# W500A.net
KiCad netlist of a schematic drawn in EAGLE
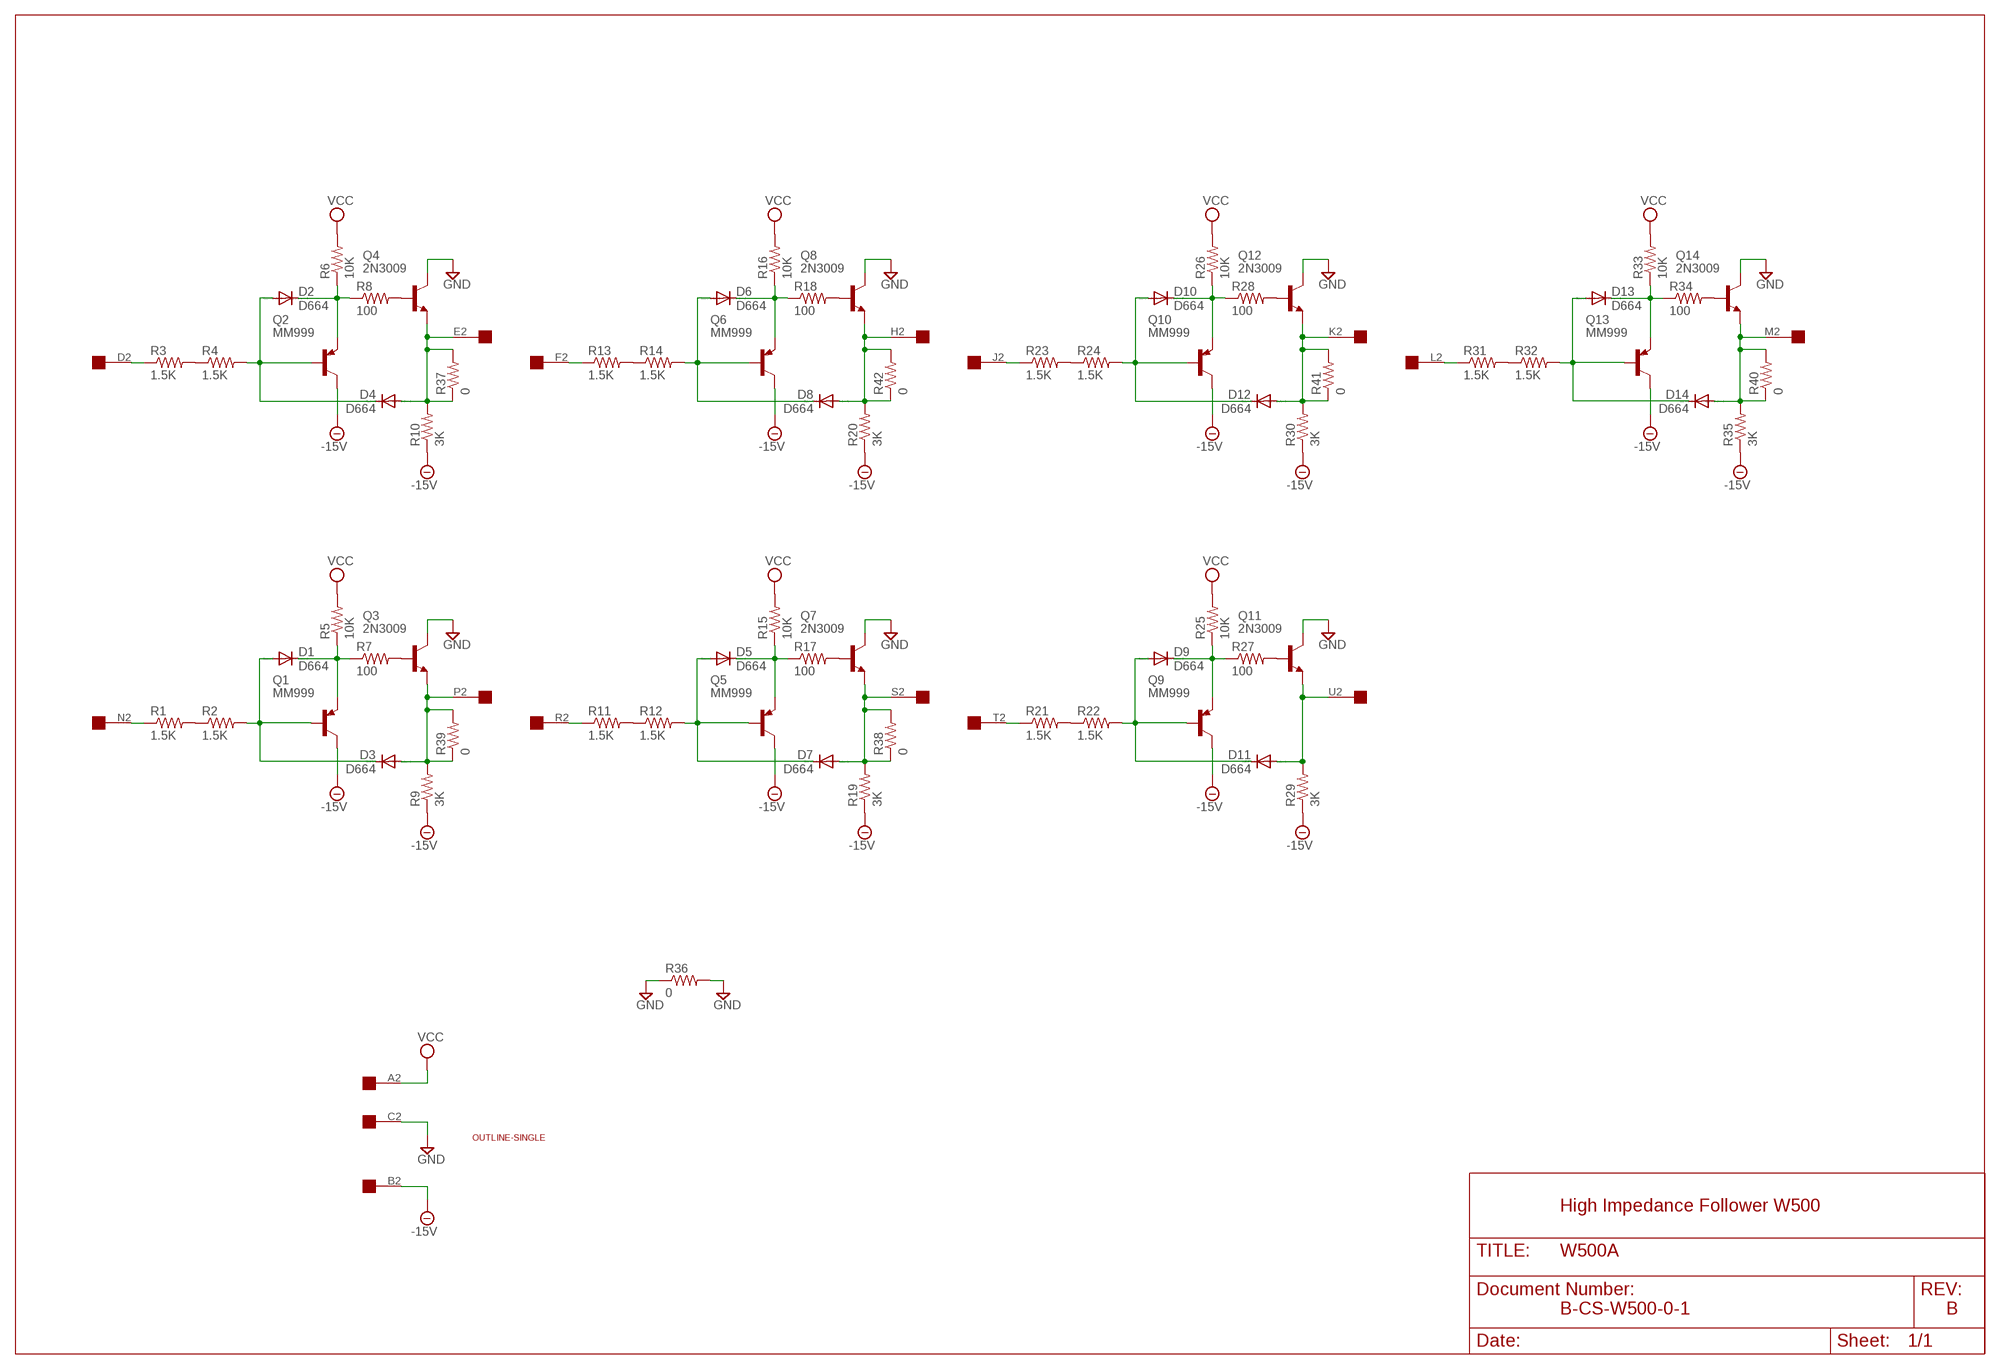
[diagram p0: schematic, sheet 1]

(export (version "E")
  (design (tool "Eeschema 10.0.6"))
  (components
    (comp (ref "D1")
      (value "D664")
      (footprint "eagle-import:DO35-10")
      (libsource (lib "eagle-import") (part "DIODE-DO35-10"))
    )
    (comp (ref "D2")
      (value "D664")
      (footprint "eagle-import:DO35-10")
      (libsource (lib "eagle-import") (part "DIODE-DO35-10"))
    )
    (comp (ref "D3")
      (value "D664")
      (footprint "eagle-import:DO35-10")
      (libsource (lib "eagle-import") (part "DIODE-DO35-10"))
    )
    (comp (ref "D4")
      (value "D664")
      (footprint "eagle-import:DO35-10")
      (libsource (lib "eagle-import") (part "DIODE-DO35-10"))
    )
    (comp (ref "D5")
      (value "D664")
      (footprint "eagle-import:DO35-10")
      (libsource (lib "eagle-import") (part "DIODE-DO35-10"))
    )
    (comp (ref "D6")
      (value "D664")
      (footprint "eagle-import:DO35-10")
      (libsource (lib "eagle-import") (part "DIODE-DO35-10"))
    )
    (comp (ref "D7")
      (value "D664")
      (footprint "eagle-import:DO35-10")
      (libsource (lib "eagle-import") (part "DIODE-DO35-10"))
    )
    (comp (ref "D8")
      (value "D664")
      (footprint "eagle-import:DO35-10")
      (libsource (lib "eagle-import") (part "DIODE-DO35-10"))
    )
    (comp (ref "D9")
      (value "D664")
      (footprint "eagle-import:DO35-10")
      (libsource (lib "eagle-import") (part "DIODE-DO35-10"))
    )
    (comp (ref "D10")
      (value "D664")
      (footprint "eagle-import:DO35-10")
      (libsource (lib "eagle-import") (part "DIODE-DO35-10"))
    )
    (comp (ref "D11")
      (value "D664")
      (footprint "eagle-import:DO35-10")
      (libsource (lib "eagle-import") (part "DIODE-DO35-10"))
    )
    (comp (ref "D12")
      (value "D664")
      (footprint "eagle-import:DO35-10")
      (libsource (lib "eagle-import") (part "DIODE-DO35-10"))
    )
    (comp (ref "D13")
      (value "D664")
      (footprint "eagle-import:DO35-10")
      (libsource (lib "eagle-import") (part "DIODE-DO35-10"))
    )
    (comp (ref "D14")
      (value "D664")
      (footprint "eagle-import:DO35-10")
      (libsource (lib "eagle-import") (part "DIODE-DO35-10"))
    )
    (comp (ref "Q1")
      (value "MM999")
      (footprint "eagle-import:TO5")
      (libsource (lib "eagle-import") (part "-PNP-TO5"))
    )
    (comp (ref "Q2")
      (value "MM999")
      (footprint "eagle-import:TO5")
      (libsource (lib "eagle-import") (part "-PNP-TO5"))
    )
    (comp (ref "Q3")
      (value "2N3009")
      (footprint "eagle-import:TO5")
      (libsource (lib "eagle-import") (part "-NPN-TO5"))
    )
    (comp (ref "Q4")
      (value "2N3009")
      (footprint "eagle-import:TO5")
      (libsource (lib "eagle-import") (part "-NPN-TO5"))
    )
    (comp (ref "Q5")
      (value "MM999")
      (footprint "eagle-import:TO5")
      (libsource (lib "eagle-import") (part "-PNP-TO5"))
    )
    (comp (ref "Q6")
      (value "MM999")
      (footprint "eagle-import:TO5")
      (libsource (lib "eagle-import") (part "-PNP-TO5"))
    )
    (comp (ref "Q7")
      (value "2N3009")
      (footprint "eagle-import:TO5")
      (libsource (lib "eagle-import") (part "-NPN-TO5"))
    )
    (comp (ref "Q8")
      (value "2N3009")
      (footprint "eagle-import:TO5")
      (libsource (lib "eagle-import") (part "-NPN-TO5"))
    )
    (comp (ref "Q9")
      (value "MM999")
      (footprint "eagle-import:TO5")
      (libsource (lib "eagle-import") (part "-PNP-TO5"))
    )
    (comp (ref "Q10")
      (value "MM999")
      (footprint "eagle-import:TO5")
      (libsource (lib "eagle-import") (part "-PNP-TO5"))
    )
    (comp (ref "Q11")
      (value "2N3009")
      (footprint "eagle-import:TO5")
      (libsource (lib "eagle-import") (part "-NPN-TO5"))
    )
    (comp (ref "Q12")
      (value "2N3009")
      (footprint "eagle-import:TO5")
      (libsource (lib "eagle-import") (part "-NPN-TO5"))
    )
    (comp (ref "Q13")
      (value "MM999")
      (footprint "eagle-import:TO5")
      (libsource (lib "eagle-import") (part "-PNP-TO5"))
    )
    (comp (ref "Q14")
      (value "2N3009")
      (footprint "eagle-import:TO5")
      (libsource (lib "eagle-import") (part "-NPN-TO5"))
    )
    (comp (ref "R1")
      (value "1.5K")
      (footprint "eagle-import:0207_10")
      (libsource (lib "eagle-import") (part "R-US_0207/10"))
    )
    (comp (ref "R2")
      (value "1.5K")
      (footprint "eagle-import:0207_10")
      (libsource (lib "eagle-import") (part "R-US_0207/10"))
    )
    (comp (ref "R3")
      (value "1.5K")
      (footprint "eagle-import:0207_10")
      (libsource (lib "eagle-import") (part "R-US_0207/10"))
    )
    (comp (ref "R4")
      (value "1.5K")
      (footprint "eagle-import:0207_10")
      (libsource (lib "eagle-import") (part "R-US_0207/10"))
    )
    (comp (ref "R5")
      (value "10K")
      (footprint "eagle-import:0207_10")
      (libsource (lib "eagle-import") (part "R-US_0207/10"))
    )
    (comp (ref "R6")
      (value "10K")
      (footprint "eagle-import:0207_10")
      (libsource (lib "eagle-import") (part "R-US_0207/10"))
    )
    (comp (ref "R7")
      (value "100")
      (footprint "eagle-import:0207_10")
      (libsource (lib "eagle-import") (part "R-US_0207/10"))
    )
    (comp (ref "R8")
      (value "100")
      (footprint "eagle-import:0207_10")
      (libsource (lib "eagle-import") (part "R-US_0207/10"))
    )
    (comp (ref "R9")
      (value "3K")
      (footprint "eagle-import:0207_10")
      (libsource (lib "eagle-import") (part "R-US_0207/10"))
    )
    (comp (ref "R10")
      (value "3K")
      (footprint "eagle-import:0207_10")
      (libsource (lib "eagle-import") (part "R-US_0207/10"))
    )
    (comp (ref "R11")
      (value "1.5K")
      (footprint "eagle-import:0207_10")
      (libsource (lib "eagle-import") (part "R-US_0207/10"))
    )
    (comp (ref "R12")
      (value "1.5K")
      (footprint "eagle-import:0207_10")
      (libsource (lib "eagle-import") (part "R-US_0207/10"))
    )
    (comp (ref "R13")
      (value "1.5K")
      (footprint "eagle-import:0207_10")
      (libsource (lib "eagle-import") (part "R-US_0207/10"))
    )
    (comp (ref "R14")
      (value "1.5K")
      (footprint "eagle-import:0207_10")
      (libsource (lib "eagle-import") (part "R-US_0207/10"))
    )
    (comp (ref "R15")
      (value "10K")
      (footprint "eagle-import:0207_10")
      (libsource (lib "eagle-import") (part "R-US_0207/10"))
    )
    (comp (ref "R16")
      (value "10K")
      (footprint "eagle-import:0207_10")
      (libsource (lib "eagle-import") (part "R-US_0207/10"))
    )
    (comp (ref "R17")
      (value "100")
      (footprint "eagle-import:0207_10")
      (libsource (lib "eagle-import") (part "R-US_0207/10"))
    )
    (comp (ref "R18")
      (value "100")
      (footprint "eagle-import:0207_10")
      (libsource (lib "eagle-import") (part "R-US_0207/10"))
    )
    (comp (ref "R19")
      (value "3K")
      (footprint "eagle-import:0207_10")
      (libsource (lib "eagle-import") (part "R-US_0207/10"))
    )
    (comp (ref "R20")
      (value "3K")
      (footprint "eagle-import:0207_10")
      (libsource (lib "eagle-import") (part "R-US_0207/10"))
    )
    (comp (ref "R21")
      (value "1.5K")
      (footprint "eagle-import:0207_10")
      (libsource (lib "eagle-import") (part "R-US_0207/10"))
    )
    (comp (ref "R22")
      (value "1.5K")
      (footprint "eagle-import:0207_10")
      (libsource (lib "eagle-import") (part "R-US_0207/10"))
    )
    (comp (ref "R23")
      (value "1.5K")
      (footprint "eagle-import:0207_10")
      (libsource (lib "eagle-import") (part "R-US_0207/10"))
    )
    (comp (ref "R24")
      (value "1.5K")
      (footprint "eagle-import:0207_10")
      (libsource (lib "eagle-import") (part "R-US_0207/10"))
    )
    (comp (ref "R25")
      (value "10K")
      (footprint "eagle-import:0207_10")
      (libsource (lib "eagle-import") (part "R-US_0207/10"))
    )
    (comp (ref "R26")
      (value "10K")
      (footprint "eagle-import:0207_10")
      (libsource (lib "eagle-import") (part "R-US_0207/10"))
    )
    (comp (ref "R27")
      (value "100")
      (footprint "eagle-import:0207_10")
      (libsource (lib "eagle-import") (part "R-US_0207/10"))
    )
    (comp (ref "R28")
      (value "100")
      (footprint "eagle-import:0207_10")
      (libsource (lib "eagle-import") (part "R-US_0207/10"))
    )
    (comp (ref "R29")
      (value "3K")
      (footprint "eagle-import:0207_10")
      (libsource (lib "eagle-import") (part "R-US_0207/10"))
    )
    (comp (ref "R30")
      (value "3K")
      (footprint "eagle-import:0207_10")
      (libsource (lib "eagle-import") (part "R-US_0207/10"))
    )
    (comp (ref "R31")
      (value "1.5K")
      (footprint "eagle-import:0207_10")
      (libsource (lib "eagle-import") (part "R-US_0207/10"))
    )
    (comp (ref "R32")
      (value "1.5K")
      (footprint "eagle-import:0207_10")
      (libsource (lib "eagle-import") (part "R-US_0207/10"))
    )
    (comp (ref "R33")
      (value "10K")
      (footprint "eagle-import:0207_10")
      (libsource (lib "eagle-import") (part "R-US_0207/10"))
    )
    (comp (ref "R34")
      (value "100")
      (footprint "eagle-import:0207_10")
      (libsource (lib "eagle-import") (part "R-US_0207/10"))
    )
    (comp (ref "R35")
      (value "3K")
      (footprint "eagle-import:0207_10")
      (libsource (lib "eagle-import") (part "R-US_0207/10"))
    )
    (comp (ref "R36")
      (value "0")
      (footprint "eagle-import:0207_10")
      (libsource (lib "eagle-import") (part "R-US_0207/10"))
    )
    (comp (ref "R37")
      (value "0")
      (footprint "eagle-import:0207_10")
      (libsource (lib "eagle-import") (part "R-US_0207/10"))
    )
    (comp (ref "R38")
      (value "0")
      (footprint "eagle-import:0207_10")
      (libsource (lib "eagle-import") (part "R-US_0207/10"))
    )
    (comp (ref "R39")
      (value "0")
      (footprint "eagle-import:0207_10")
      (libsource (lib "eagle-import") (part "R-US_0207/10"))
    )
    (comp (ref "R40")
      (value "0")
      (footprint "eagle-import:0207_10")
      (libsource (lib "eagle-import") (part "R-US_0207/10"))
    )
    (comp (ref "R41")
      (value "0")
      (footprint "eagle-import:0207_10")
      (libsource (lib "eagle-import") (part "R-US_0207/10"))
    )
    (comp (ref "R42")
      (value "0")
      (footprint "eagle-import:0207_10")
      (libsource (lib "eagle-import") (part "R-US_0207/10"))
    )
    (comp (ref "U$1")
      (value "OUTLINE-SINGLE")
      (footprint "eagle-import:SINGLE")
      (libsource (lib "eagle-import") (part "OUTLINE-SINGLE"))
    )
    (comp (ref "U$2")
      (value "EDGE-1")
      (footprint "eagle-import:EDGE-CON1")
      (libsource (lib "eagle-import") (part "EDGE-1"))
    )
  )
  (nets
    (net (code "1") (name "-15V") (class "Default")
      (node (ref "Q1") (pin "3") (pinfunction "C_3") (pintype "passive"))
      (node (ref "Q10") (pin "3") (pinfunction "C_3") (pintype "passive"))
      (node (ref "Q13") (pin "3") (pinfunction "C_3") (pintype "passive"))
      (node (ref "Q2") (pin "3") (pinfunction "C_3") (pintype "passive"))
      (node (ref "Q5") (pin "3") (pinfunction "C_3") (pintype "passive"))
      (node (ref "Q6") (pin "3") (pinfunction "C_3") (pintype "passive"))
      (node (ref "Q9") (pin "3") (pinfunction "C_3") (pintype "passive"))
      (node (ref "R10") (pin "1") (pinfunction "1_1") (pintype "passive"))
      (node (ref "R19") (pin "1") (pinfunction "1_1") (pintype "passive"))
      (node (ref "R20") (pin "1") (pinfunction "1_1") (pintype "passive"))
      (node (ref "R29") (pin "1") (pinfunction "1_1") (pintype "passive"))
      (node (ref "R30") (pin "1") (pinfunction "1_1") (pintype "passive"))
      (node (ref "R35") (pin "1") (pinfunction "1_1") (pintype "passive"))
      (node (ref "R9") (pin "1") (pinfunction "1_1") (pintype "passive"))
      (node (ref "U$2") (pin "B2") (pinfunction "1_B2") (pintype "bidirectional"))
    )
    (net (code "2") (name "GND") (class "Default")
      (node (ref "Q11") (pin "3") (pinfunction "C_3") (pintype "passive"))
      (node (ref "Q12") (pin "3") (pinfunction "C_3") (pintype "passive"))
      (node (ref "Q14") (pin "3") (pinfunction "C_3") (pintype "passive"))
      (node (ref "Q3") (pin "3") (pinfunction "C_3") (pintype "passive"))
      (node (ref "Q4") (pin "3") (pinfunction "C_3") (pintype "passive"))
      (node (ref "Q7") (pin "3") (pinfunction "C_3") (pintype "passive"))
      (node (ref "Q8") (pin "3") (pinfunction "C_3") (pintype "passive"))
      (node (ref "R36") (pin "1") (pinfunction "1_1") (pintype "passive"))
      (node (ref "R36") (pin "2") (pinfunction "2_2") (pintype "passive"))
      (node (ref "U$2") (pin "C2") (pinfunction "1_C2") (pintype "bidirectional"))
    )
    (net (code "3") (name "Net-(Q1-B)") (class "Default")
      (node (ref "D1") (pin "A") (pinfunction "A_A") (pintype "passive"))
      (node (ref "D3") (pin "C") (pinfunction "C_C") (pintype "passive"))
      (node (ref "Q1") (pin "2") (pinfunction "B_2") (pintype "passive"))
      (node (ref "R2") (pin "2") (pinfunction "2_2") (pintype "passive"))
    )
    (net (code "4") (name "Net-(Q1-E)") (class "Default")
      (node (ref "D1") (pin "C") (pinfunction "C_C") (pintype "passive"))
      (node (ref "Q1") (pin "1") (pinfunction "E_1") (pintype "passive"))
      (node (ref "R5") (pin "1") (pinfunction "1_1") (pintype "passive"))
      (node (ref "R7") (pin "1") (pinfunction "1_1") (pintype "passive"))
    )
    (net (code "5") (name "Net-(Q2-B)") (class "Default")
      (node (ref "D2") (pin "A") (pinfunction "A_A") (pintype "passive"))
      (node (ref "D4") (pin "C") (pinfunction "C_C") (pintype "passive"))
      (node (ref "Q2") (pin "2") (pinfunction "B_2") (pintype "passive"))
      (node (ref "R4") (pin "2") (pinfunction "2_2") (pintype "passive"))
    )
    (net (code "6") (name "Net-(Q2-E)") (class "Default")
      (node (ref "D2") (pin "C") (pinfunction "C_C") (pintype "passive"))
      (node (ref "Q2") (pin "1") (pinfunction "E_1") (pintype "passive"))
      (node (ref "R6") (pin "1") (pinfunction "1_1") (pintype "passive"))
      (node (ref "R8") (pin "1") (pinfunction "1_1") (pintype "passive"))
    )
    (net (code "7") (name "Net-(Q3-B)") (class "Default")
      (node (ref "Q3") (pin "2") (pinfunction "B_2") (pintype "passive"))
      (node (ref "R7") (pin "2") (pinfunction "2_2") (pintype "passive"))
    )
    (net (code "8") (name "Net-(Q3-E)") (class "Default")
      (node (ref "D3") (pin "A") (pinfunction "A_A") (pintype "passive"))
      (node (ref "Q3") (pin "1") (pinfunction "E_1") (pintype "passive"))
      (node (ref "R39") (pin "1") (pinfunction "1_1") (pintype "passive"))
      (node (ref "R39") (pin "2") (pinfunction "2_2") (pintype "passive"))
      (node (ref "R9") (pin "2") (pinfunction "2_2") (pintype "passive"))
      (node (ref "U$2") (pin "P2") (pinfunction "1_P2") (pintype "bidirectional"))
    )
    (net (code "9") (name "Net-(Q4-B)") (class "Default")
      (node (ref "Q4") (pin "2") (pinfunction "B_2") (pintype "passive"))
      (node (ref "R8") (pin "2") (pinfunction "2_2") (pintype "passive"))
    )
    (net (code "10") (name "Net-(Q4-E)") (class "Default")
      (node (ref "D4") (pin "A") (pinfunction "A_A") (pintype "passive"))
      (node (ref "Q4") (pin "1") (pinfunction "E_1") (pintype "passive"))
      (node (ref "R10") (pin "2") (pinfunction "2_2") (pintype "passive"))
      (node (ref "R37") (pin "1") (pinfunction "1_1") (pintype "passive"))
      (node (ref "R37") (pin "2") (pinfunction "2_2") (pintype "passive"))
      (node (ref "U$2") (pin "E2") (pinfunction "1_E2") (pintype "bidirectional"))
    )
    (net (code "11") (name "Net-(Q5-B)") (class "Default")
      (node (ref "D5") (pin "A") (pinfunction "A_A") (pintype "passive"))
      (node (ref "D7") (pin "C") (pinfunction "C_C") (pintype "passive"))
      (node (ref "Q5") (pin "2") (pinfunction "B_2") (pintype "passive"))
      (node (ref "R12") (pin "2") (pinfunction "2_2") (pintype "passive"))
    )
    (net (code "12") (name "Net-(Q5-E)") (class "Default")
      (node (ref "D5") (pin "C") (pinfunction "C_C") (pintype "passive"))
      (node (ref "Q5") (pin "1") (pinfunction "E_1") (pintype "passive"))
      (node (ref "R15") (pin "1") (pinfunction "1_1") (pintype "passive"))
      (node (ref "R17") (pin "1") (pinfunction "1_1") (pintype "passive"))
    )
    (net (code "13") (name "Net-(Q6-B)") (class "Default")
      (node (ref "D6") (pin "A") (pinfunction "A_A") (pintype "passive"))
      (node (ref "D8") (pin "C") (pinfunction "C_C") (pintype "passive"))
      (node (ref "Q6") (pin "2") (pinfunction "B_2") (pintype "passive"))
      (node (ref "R14") (pin "2") (pinfunction "2_2") (pintype "passive"))
    )
    (net (code "14") (name "Net-(Q6-E)") (class "Default")
      (node (ref "D6") (pin "C") (pinfunction "C_C") (pintype "passive"))
      (node (ref "Q6") (pin "1") (pinfunction "E_1") (pintype "passive"))
      (node (ref "R16") (pin "1") (pinfunction "1_1") (pintype "passive"))
      (node (ref "R18") (pin "1") (pinfunction "1_1") (pintype "passive"))
    )
    (net (code "15") (name "Net-(Q7-B)") (class "Default")
      (node (ref "Q7") (pin "2") (pinfunction "B_2") (pintype "passive"))
      (node (ref "R17") (pin "2") (pinfunction "2_2") (pintype "passive"))
    )
    (net (code "16") (name "Net-(Q7-E)") (class "Default")
      (node (ref "D7") (pin "A") (pinfunction "A_A") (pintype "passive"))
      (node (ref "Q7") (pin "1") (pinfunction "E_1") (pintype "passive"))
      (node (ref "R19") (pin "2") (pinfunction "2_2") (pintype "passive"))
      (node (ref "R38") (pin "1") (pinfunction "1_1") (pintype "passive"))
      (node (ref "R38") (pin "2") (pinfunction "2_2") (pintype "passive"))
      (node (ref "U$2") (pin "S2") (pinfunction "1_S2") (pintype "bidirectional"))
    )
    (net (code "17") (name "Net-(Q8-B)") (class "Default")
      (node (ref "Q8") (pin "2") (pinfunction "B_2") (pintype "passive"))
      (node (ref "R18") (pin "2") (pinfunction "2_2") (pintype "passive"))
    )
    (net (code "18") (name "Net-(Q8-E)") (class "Default")
      (node (ref "D8") (pin "A") (pinfunction "A_A") (pintype "passive"))
      (node (ref "Q8") (pin "1") (pinfunction "E_1") (pintype "passive"))
      (node (ref "R20") (pin "2") (pinfunction "2_2") (pintype "passive"))
      (node (ref "R42") (pin "1") (pinfunction "1_1") (pintype "passive"))
      (node (ref "R42") (pin "2") (pinfunction "2_2") (pintype "passive"))
      (node (ref "U$2") (pin "H2") (pinfunction "1_H2") (pintype "bidirectional"))
    )
    (net (code "19") (name "Net-(Q9-B)") (class "Default")
      (node (ref "D11") (pin "C") (pinfunction "C_C") (pintype "passive"))
      (node (ref "D9") (pin "A") (pinfunction "A_A") (pintype "passive"))
      (node (ref "Q9") (pin "2") (pinfunction "B_2") (pintype "passive"))
      (node (ref "R22") (pin "2") (pinfunction "2_2") (pintype "passive"))
    )
    (net (code "20") (name "Net-(Q9-E)") (class "Default")
      (node (ref "D9") (pin "C") (pinfunction "C_C") (pintype "passive"))
      (node (ref "Q9") (pin "1") (pinfunction "E_1") (pintype "passive"))
      (node (ref "R25") (pin "1") (pinfunction "1_1") (pintype "passive"))
      (node (ref "R27") (pin "1") (pinfunction "1_1") (pintype "passive"))
    )
    (net (code "21") (name "Net-(Q10-B)") (class "Default")
      (node (ref "D10") (pin "A") (pinfunction "A_A") (pintype "passive"))
      (node (ref "D12") (pin "C") (pinfunction "C_C") (pintype "passive"))
      (node (ref "Q10") (pin "2") (pinfunction "B_2") (pintype "passive"))
      (node (ref "R24") (pin "2") (pinfunction "2_2") (pintype "passive"))
    )
    (net (code "22") (name "Net-(Q10-E)") (class "Default")
      (node (ref "D10") (pin "C") (pinfunction "C_C") (pintype "passive"))
      (node (ref "Q10") (pin "1") (pinfunction "E_1") (pintype "passive"))
      (node (ref "R26") (pin "1") (pinfunction "1_1") (pintype "passive"))
      (node (ref "R28") (pin "1") (pinfunction "1_1") (pintype "passive"))
    )
    (net (code "23") (name "Net-(Q11-B)") (class "Default")
      (node (ref "Q11") (pin "2") (pinfunction "B_2") (pintype "passive"))
      (node (ref "R27") (pin "2") (pinfunction "2_2") (pintype "passive"))
    )
    (net (code "24") (name "Net-(Q11-E)") (class "Default")
      (node (ref "D11") (pin "A") (pinfunction "A_A") (pintype "passive"))
      (node (ref "Q11") (pin "1") (pinfunction "E_1") (pintype "passive"))
      (node (ref "R29") (pin "2") (pinfunction "2_2") (pintype "passive"))
      (node (ref "U$2") (pin "U2") (pinfunction "1_U2") (pintype "bidirectional"))
    )
    (net (code "25") (name "Net-(Q12-B)") (class "Default")
      (node (ref "Q12") (pin "2") (pinfunction "B_2") (pintype "passive"))
      (node (ref "R28") (pin "2") (pinfunction "2_2") (pintype "passive"))
    )
    (net (code "26") (name "Net-(Q12-E)") (class "Default")
      (node (ref "D12") (pin "A") (pinfunction "A_A") (pintype "passive"))
      (node (ref "Q12") (pin "1") (pinfunction "E_1") (pintype "passive"))
      (node (ref "R30") (pin "2") (pinfunction "2_2") (pintype "passive"))
      (node (ref "R41") (pin "1") (pinfunction "1_1") (pintype "passive"))
      (node (ref "R41") (pin "2") (pinfunction "2_2") (pintype "passive"))
      (node (ref "U$2") (pin "K2") (pinfunction "1_K2") (pintype "bidirectional"))
    )
    (net (code "27") (name "Net-(Q13-B)") (class "Default")
      (node (ref "D13") (pin "A") (pinfunction "A_A") (pintype "passive"))
      (node (ref "D14") (pin "C") (pinfunction "C_C") (pintype "passive"))
      (node (ref "Q13") (pin "2") (pinfunction "B_2") (pintype "passive"))
      (node (ref "R32") (pin "2") (pinfunction "2_2") (pintype "passive"))
    )
    (net (code "28") (name "Net-(Q13-E)") (class "Default")
      (node (ref "D13") (pin "C") (pinfunction "C_C") (pintype "passive"))
      (node (ref "Q13") (pin "1") (pinfunction "E_1") (pintype "passive"))
      (node (ref "R33") (pin "1") (pinfunction "1_1") (pintype "passive"))
      (node (ref "R34") (pin "1") (pinfunction "1_1") (pintype "passive"))
    )
    (net (code "29") (name "Net-(Q14-B)") (class "Default")
      (node (ref "Q14") (pin "2") (pinfunction "B_2") (pintype "passive"))
      (node (ref "R34") (pin "2") (pinfunction "2_2") (pintype "passive"))
    )
    (net (code "30") (name "Net-(Q14-E)") (class "Default")
      (node (ref "D14") (pin "A") (pinfunction "A_A") (pintype "passive"))
      (node (ref "Q14") (pin "1") (pinfunction "E_1") (pintype "passive"))
      (node (ref "R35") (pin "2") (pinfunction "2_2") (pintype "passive"))
      (node (ref "R40") (pin "1") (pinfunction "1_1") (pintype "passive"))
      (node (ref "R40") (pin "2") (pinfunction "2_2") (pintype "passive"))
      (node (ref "U$2") (pin "M2") (pinfunction "1_M2") (pintype "bidirectional"))
    )
    (net (code "31") (name "Net-(R1-Pad2)") (class "Default")
      (node (ref "R1") (pin "2") (pinfunction "2_2") (pintype "passive"))
      (node (ref "R2") (pin "1") (pinfunction "1_1") (pintype "passive"))
    )
    (net (code "32") (name "Net-(R3-Pad2)") (class "Default")
      (node (ref "R3") (pin "2") (pinfunction "2_2") (pintype "passive"))
      (node (ref "R4") (pin "1") (pinfunction "1_1") (pintype "passive"))
    )
    (net (code "33") (name "Net-(R11-Pad2)") (class "Default")
      (node (ref "R11") (pin "2") (pinfunction "2_2") (pintype "passive"))
      (node (ref "R12") (pin "1") (pinfunction "1_1") (pintype "passive"))
    )
    (net (code "34") (name "Net-(R13-Pad2)") (class "Default")
      (node (ref "R13") (pin "2") (pinfunction "2_2") (pintype "passive"))
      (node (ref "R14") (pin "1") (pinfunction "1_1") (pintype "passive"))
    )
    (net (code "35") (name "Net-(R21-Pad2)") (class "Default")
      (node (ref "R21") (pin "2") (pinfunction "2_2") (pintype "passive"))
      (node (ref "R22") (pin "1") (pinfunction "1_1") (pintype "passive"))
    )
    (net (code "36") (name "Net-(R23-Pad2)") (class "Default")
      (node (ref "R23") (pin "2") (pinfunction "2_2") (pintype "passive"))
      (node (ref "R24") (pin "1") (pinfunction "1_1") (pintype "passive"))
    )
    (net (code "37") (name "Net-(R31-Pad2)") (class "Default")
      (node (ref "R31") (pin "2") (pinfunction "2_2") (pintype "passive"))
      (node (ref "R32") (pin "1") (pinfunction "1_1") (pintype "passive"))
    )
    (net (code "38") (name "Net-(U$2D-1)") (class "Default")
      (node (ref "R3") (pin "1") (pinfunction "1_1") (pintype "passive"))
      (node (ref "U$2") (pin "D2") (pinfunction "1_D2") (pintype "bidirectional"))
    )
    (net (code "39") (name "Net-(U$2F-1)") (class "Default")
      (node (ref "R13") (pin "1") (pinfunction "1_1") (pintype "passive"))
      (node (ref "U$2") (pin "F2") (pinfunction "1_F2") (pintype "bidirectional"))
    )
    (net (code "40") (name "Net-(U$2H-1)") (class "Default")
      (node (ref "R23") (pin "1") (pinfunction "1_1") (pintype "passive"))
      (node (ref "U$2") (pin "J2") (pinfunction "1_J2") (pintype "bidirectional"))
    )
    (net (code "41") (name "Net-(U$2J-1)") (class "Default")
      (node (ref "R31") (pin "1") (pinfunction "1_1") (pintype "passive"))
      (node (ref "U$2") (pin "L2") (pinfunction "1_L2") (pintype "bidirectional"))
    )
    (net (code "42") (name "Net-(U$2L-1)") (class "Default")
      (node (ref "R1") (pin "1") (pinfunction "1_1") (pintype "passive"))
      (node (ref "U$2") (pin "N2") (pinfunction "1_N2") (pintype "bidirectional"))
    )
    (net (code "43") (name "Net-(U$2N-1)") (class "Default")
      (node (ref "R11") (pin "1") (pinfunction "1_1") (pintype "passive"))
      (node (ref "U$2") (pin "R2") (pinfunction "1_R2") (pintype "bidirectional"))
    )
    (net (code "44") (name "Net-(U$2P-1)") (class "Default")
      (node (ref "R21") (pin "1") (pinfunction "1_1") (pintype "passive"))
      (node (ref "U$2") (pin "T2") (pinfunction "1_T2") (pintype "bidirectional"))
    )
    (net (code "45") (name "VCC") (class "Default")
      (node (ref "R15") (pin "2") (pinfunction "2_2") (pintype "passive"))
      (node (ref "R16") (pin "2") (pinfunction "2_2") (pintype "passive"))
      (node (ref "R25") (pin "2") (pinfunction "2_2") (pintype "passive"))
      (node (ref "R26") (pin "2") (pinfunction "2_2") (pintype "passive"))
      (node (ref "R33") (pin "2") (pinfunction "2_2") (pintype "passive"))
      (node (ref "R5") (pin "2") (pinfunction "2_2") (pintype "passive"))
      (node (ref "R6") (pin "2") (pinfunction "2_2") (pintype "passive"))
      (node (ref "U$2") (pin "A2") (pinfunction "1_A2") (pintype "bidirectional"))
    )
  )
)
